# Domino_Single_Ethernet_No_Teardrop.net
KiCad netlist of a schematic drawn in EAGLE
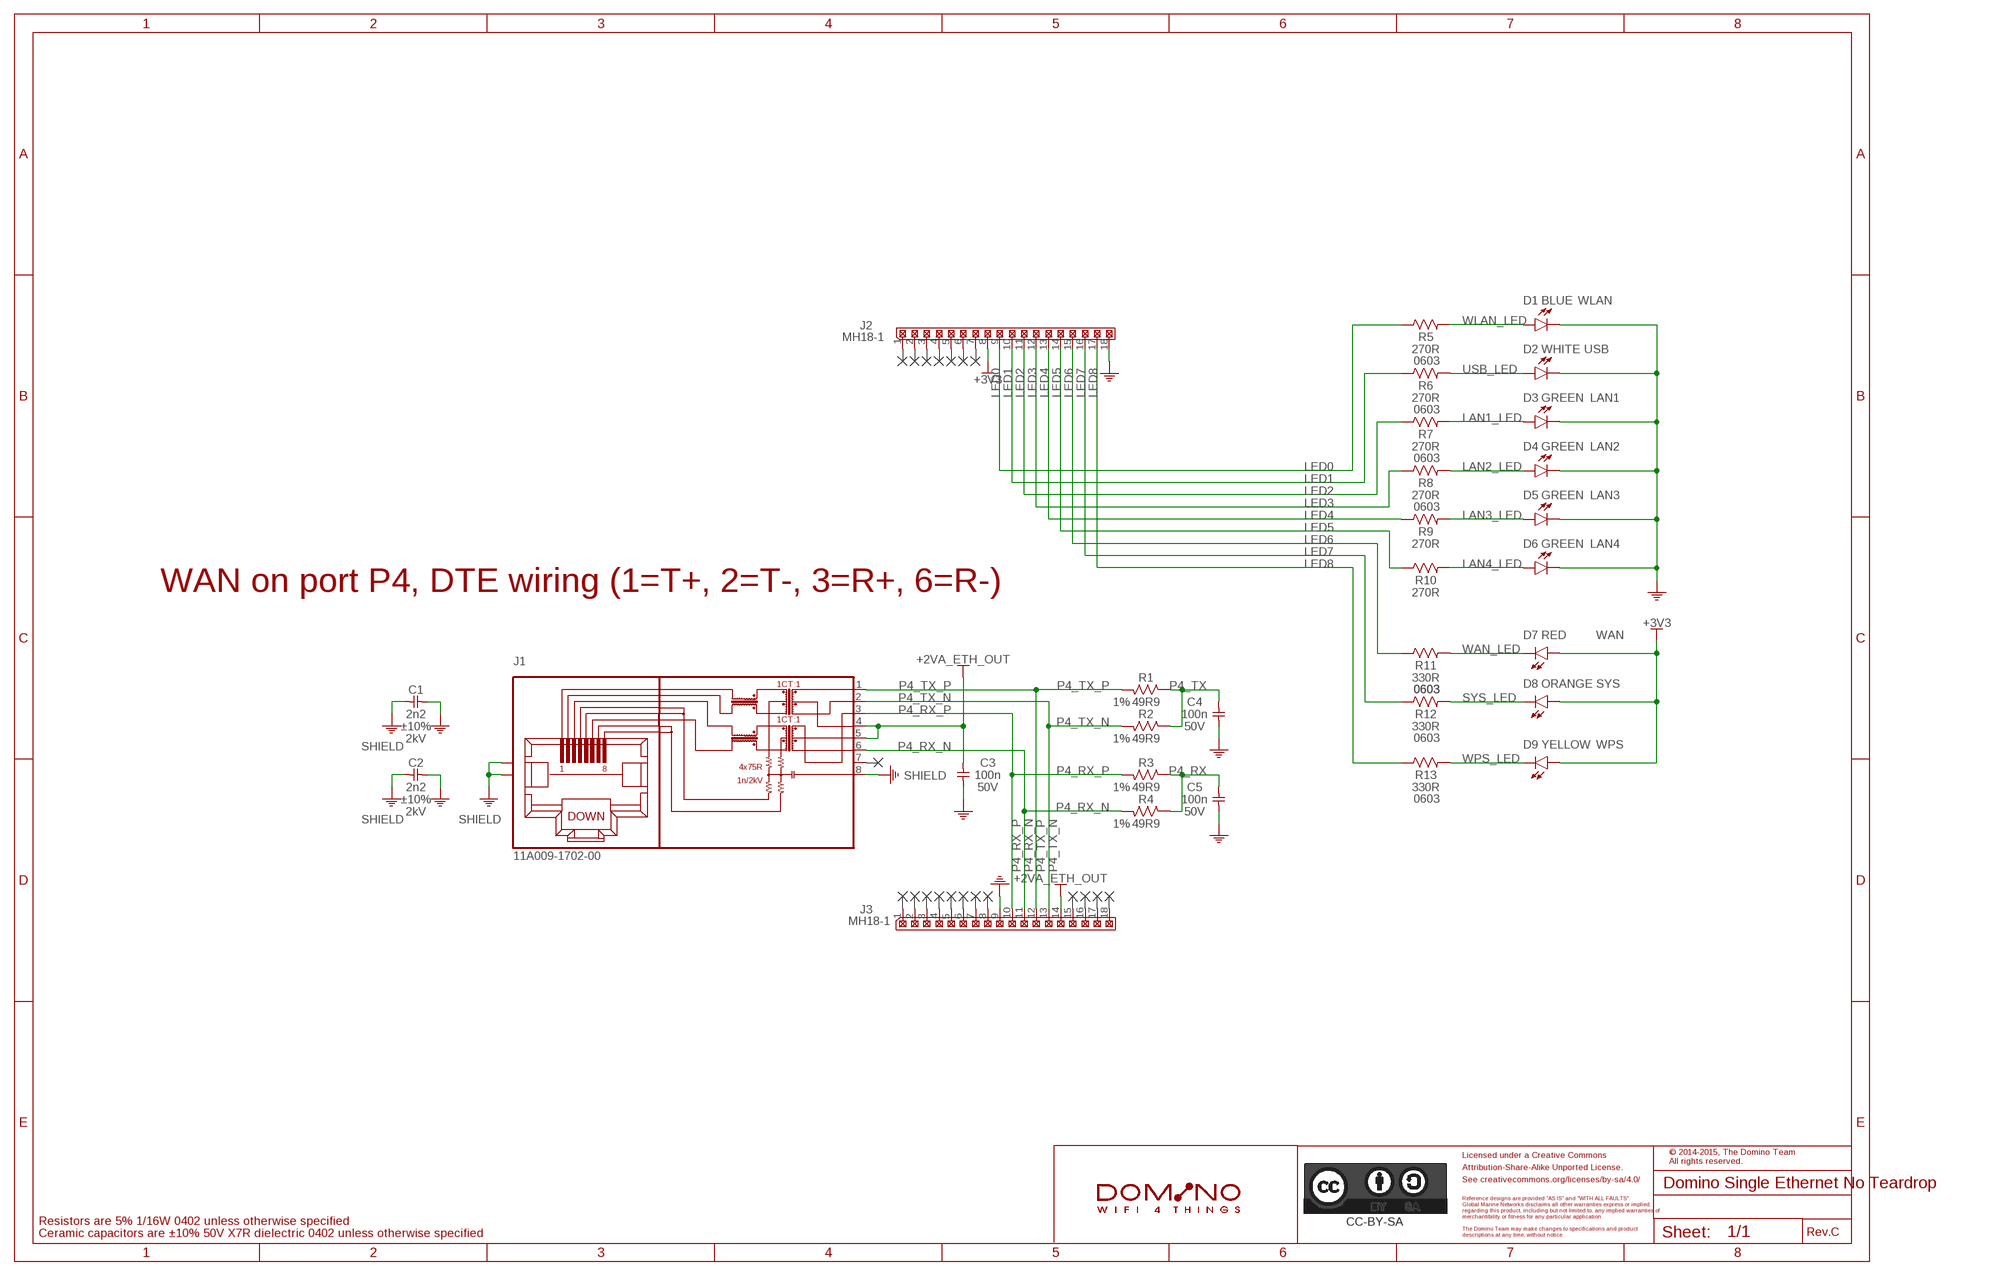
[diagram p0: schematic, sheet 1]

(export (version "E")
  (design (tool "Eeschema 10.0.6"))
  (components
    (comp (ref "C1")
      (value "2n2")
      (footprint "eagle-import:C1206")
      (fields
        (field (name "PARTNO") "C1210_2n2_X7R_10%_CER_2kV")
        (field (name "TOL") "±10%")
        (field (name "VOLT") "2kV")
      )
      (libsource (lib "eagle-import") (part "CAP_1206"))
    )
    (comp (ref "C2")
      (value "2n2")
      (footprint "eagle-import:C1206")
      (fields
        (field (name "PARTNO") "C1210_2n2_X7R_10%_CER_2kV")
        (field (name "TOL") "±10%")
        (field (name "VOLT") "2kV")
      )
      (libsource (lib "eagle-import") (part "CAP_1206"))
    )
    (comp (ref "C3")
      (value "100n")
      (footprint "eagle-import:C0402")
      (fields (field (name "PARTNO") "C0402_100n_X7R_10%_CER_50V") (field (name "VOLT") "50V"))
      (libsource (lib "eagle-import") (part "CAP_0402"))
    )
    (comp (ref "C4")
      (value "100n")
      (footprint "eagle-import:C0402")
      (fields (field (name "PARTNO") "C0402_100n_X7R_10%_CER_50V") (field (name "VOLT") "50V"))
      (libsource (lib "eagle-import") (part "CAP_0402"))
    )
    (comp (ref "C5")
      (value "100n")
      (footprint "eagle-import:C0402")
      (fields (field (name "PARTNO") "C0402_100n_X7R_10%_CER_50V") (field (name "VOLT") "50V"))
      (libsource (lib "eagle-import") (part "CAP_0402"))
    )
    (comp (ref "CC-BY-SA1")
      (value "CC-BY-SA_LOGO")
      (footprint "eagle-import:CC-BY-SA_LOGO")
      (libsource (lib "eagle-import") (part "CC-BY-SA_LOGO"))
    )
    (comp (ref "D1")
      (value "BLUE")
      (footprint "eagle-import:LED0603")
      (fields (field (name "PARTNO") "LED0603-BLUE"))
      (libsource (lib "eagle-import") (part "LED_0603"))
    )
    (comp (ref "D2")
      (value "WHITE")
      (footprint "eagle-import:LED0603")
      (fields (field (name "PARTNO") "LED0603-WHITE"))
      (libsource (lib "eagle-import") (part "LED_0603"))
    )
    (comp (ref "D3")
      (value "GREEN")
      (footprint "eagle-import:LED0603")
      (fields (field (name "PARTNO") "LED0603-GREEN"))
      (libsource (lib "eagle-import") (part "LED_0603"))
    )
    (comp (ref "D4")
      (value "GREEN")
      (footprint "eagle-import:LED0603")
      (fields (field (name "PARTNO") "LED0603-GREEN"))
      (libsource (lib "eagle-import") (part "LED_0603"))
    )
    (comp (ref "D5")
      (value "GREEN")
      (footprint "eagle-import:LED0603")
      (fields (field (name "PARTNO") "LED0603-GREEN"))
      (libsource (lib "eagle-import") (part "LED_0603"))
    )
    (comp (ref "D6")
      (value "GREEN")
      (footprint "eagle-import:LED0603")
      (fields (field (name "PARTNO") "LED0603-GREEN"))
      (libsource (lib "eagle-import") (part "LED_0603"))
    )
    (comp (ref "D7")
      (value "RED")
      (footprint "eagle-import:LED0603")
      (fields (field (name "PARTNO") "LED0603-ORANGE"))
      (libsource (lib "eagle-import") (part "LED_0603"))
    )
    (comp (ref "D8")
      (value "ORANGE")
      (footprint "eagle-import:LED0603")
      (fields (field (name "PARTNO") "LED0603-ORANGE"))
      (libsource (lib "eagle-import") (part "LED_0603"))
    )
    (comp (ref "D9")
      (value "YELLOW")
      (footprint "eagle-import:LED0603")
      (fields (field (name "PARTNO") "LED0603-YELLOW"))
      (libsource (lib "eagle-import") (part "LED_0603"))
    )
    (comp (ref "J1")
      (value "11A009-1702-00")
      (footprint "eagle-import:11A009-1702-00")
      (libsource (lib "eagle-import") (part "11A009-1702-00"))
    )
    (comp (ref "J2")
      (value "MH18-1")
      (footprint "eagle-import:MH18-1-0.1")
      (fields (field (name "PARTNO") "MH18-1-0.1"))
      (libsource (lib "eagle-import") (part "MH18-1"))
    )
    (comp (ref "J3")
      (value "MH18-1")
      (footprint "eagle-import:MH18-1-0.1")
      (fields (field (name "PARTNO") "MH18-1-0.1"))
      (libsource (lib "eagle-import") (part "MH18-1"))
    )
    (comp (ref "R1")
      (value "49R9")
      (footprint "eagle-import:R0402")
      (fields (field (name "PARTNO") "R0402_49R9_1%_62.5mW") (field (name "TOL") "1%"))
      (libsource (lib "eagle-import") (part "RES_0402"))
    )
    (comp (ref "R2")
      (value "49R9")
      (footprint "eagle-import:R0402")
      (fields (field (name "PARTNO") "R0402_49R9_1%_62.5mW") (field (name "TOL") "1%"))
      (libsource (lib "eagle-import") (part "RES_0402"))
    )
    (comp (ref "R3")
      (value "49R9")
      (footprint "eagle-import:R0402")
      (fields (field (name "PARTNO") "R0402_49R9_1%_62.5mW") (field (name "TOL") "1%"))
      (libsource (lib "eagle-import") (part "RES_0402"))
    )
    (comp (ref "R4")
      (value "49R9")
      (footprint "eagle-import:R0402")
      (fields (field (name "PARTNO") "R0402_49R9_1%_62.5mW") (field (name "TOL") "1%"))
      (libsource (lib "eagle-import") (part "RES_0402"))
    )
    (comp (ref "R5")
      (value "270R")
      (footprint "eagle-import:R0603")
      (fields (field (name "SIZE") "0603") (field (name "PARTNO") "R0603_270R_5%_125mW"))
      (libsource (lib "eagle-import") (part "RES_0603"))
    )
    (comp (ref "R6")
      (value "270R")
      (footprint "eagle-import:R0603")
      (fields (field (name "SIZE") "0603") (field (name "PARTNO") "R0603_270R_5%_125mW"))
      (libsource (lib "eagle-import") (part "RES_0603"))
    )
    (comp (ref "R7")
      (value "270R")
      (footprint "eagle-import:R0603")
      (fields (field (name "SIZE") "0603") (field (name "PARTNO") "R0603_270R_5%_125mW"))
      (libsource (lib "eagle-import") (part "RES_0603"))
    )
    (comp (ref "R8")
      (value "270R")
      (footprint "eagle-import:R0603")
      (fields (field (name "SIZE") "0603") (field (name "PARTNO") "R0603_270R_5%_125mW"))
      (libsource (lib "eagle-import") (part "RES_0603"))
    )
    (comp (ref "R9")
      (value "270R")
      (footprint "eagle-import:R0603")
      (fields (field (name "PARTNO") "R0603_270R_5%_125mW"))
      (libsource (lib "eagle-import") (part "RES_0603"))
    )
    (comp (ref "R10")
      (value "270R")
      (footprint "eagle-import:R0603")
      (fields (field (name "SIZE") "0603") (field (name "PARTNO") "R0603_270R_5%_125mW"))
      (libsource (lib "eagle-import") (part "RES_0603"))
    )
    (comp (ref "R11")
      (value "330R")
      (footprint "eagle-import:R0603")
      (fields (field (name "SIZE") "0603") (field (name "PARTNO") "R0603_330R_5%_125mW"))
      (libsource (lib "eagle-import") (part "RES_0603"))
    )
    (comp (ref "R12")
      (value "330R")
      (footprint "eagle-import:R0603")
      (fields (field (name "SIZE") "0603") (field (name "PARTNO") "R0603_330R_5%_125mW"))
      (libsource (lib "eagle-import") (part "RES_0603"))
    )
    (comp (ref "R13")
      (value "330R")
      (footprint "eagle-import:R0603")
      (fields (field (name "SIZE") "0603") (field (name "PARTNO") "R0603_330R_5%_125mW"))
      (libsource (lib "eagle-import") (part "RES_0603"))
    )
    (comp (ref "U$10")
      (value "DOMINO_LOGO")
      (footprint "eagle-import:DOMINO_LOGO")
      (libsource (lib "eagle-import") (part "DOMINO_LOGO"))
    )
  )
  (nets
    (net (code "1") (name "+2VA_ETH_OUT") (class "Default")
      (node (ref "C3") (pin "2") (pinfunction "2_2") (pintype "passive"))
      (node (ref "J1") (pin "4") (pinfunction "P4_4") (pintype "passive"))
      (node (ref "J1") (pin "5") (pinfunction "P5_5") (pintype "passive"))
      (node (ref "J3") (pin "14") (pinfunction "14_14") (pintype "passive"))
    )
    (net (code "2") (name "+3V3") (class "Default")
      (node (ref "D7") (pin "2") (pinfunction "A_2") (pintype "passive"))
      (node (ref "D8") (pin "2") (pinfunction "A_2") (pintype "passive"))
      (node (ref "D9") (pin "2") (pinfunction "A_2") (pintype "passive"))
      (node (ref "J2") (pin "8") (pinfunction "8_8") (pintype "passive"))
    )
    (net (code "3") (name "/LAN1_LED") (class "Default")
      (node (ref "D3") (pin "2") (pinfunction "A_2") (pintype "passive"))
      (node (ref "R7") (pin "2") (pinfunction "2_2") (pintype "passive"))
    )
    (net (code "4") (name "/LAN2_LED") (class "Default")
      (node (ref "D4") (pin "2") (pinfunction "A_2") (pintype "passive"))
      (node (ref "R8") (pin "2") (pinfunction "2_2") (pintype "passive"))
    )
    (net (code "5") (name "/LAN3_LED") (class "Default")
      (node (ref "D5") (pin "2") (pinfunction "A_2") (pintype "passive"))
      (node (ref "R9") (pin "2") (pinfunction "2_2") (pintype "passive"))
    )
    (net (code "6") (name "/LAN4_LED") (class "Default")
      (node (ref "D6") (pin "2") (pinfunction "A_2") (pintype "passive"))
      (node (ref "R10") (pin "2") (pinfunction "2_2") (pintype "passive"))
    )
    (net (code "7") (name "/LED0") (class "Default")
      (node (ref "J2") (pin "9") (pinfunction "9_9") (pintype "passive"))
      (node (ref "R5") (pin "1") (pinfunction "1_1") (pintype "passive"))
    )
    (net (code "8") (name "/LED1") (class "Default")
      (node (ref "J2") (pin "10") (pinfunction "10_10") (pintype "passive"))
      (node (ref "R6") (pin "1") (pinfunction "1_1") (pintype "passive"))
    )
    (net (code "9") (name "/LED2") (class "Default")
      (node (ref "J2") (pin "11") (pinfunction "11_11") (pintype "passive"))
      (node (ref "R7") (pin "1") (pinfunction "1_1") (pintype "passive"))
    )
    (net (code "10") (name "/LED3") (class "Default")
      (node (ref "J2") (pin "12") (pinfunction "12_12") (pintype "passive"))
      (node (ref "R8") (pin "1") (pinfunction "1_1") (pintype "passive"))
    )
    (net (code "11") (name "/LED4") (class "Default")
      (node (ref "J2") (pin "13") (pinfunction "13_13") (pintype "passive"))
      (node (ref "R9") (pin "1") (pinfunction "1_1") (pintype "passive"))
    )
    (net (code "12") (name "/LED5") (class "Default")
      (node (ref "J2") (pin "14") (pinfunction "14_14") (pintype "passive"))
      (node (ref "R10") (pin "1") (pinfunction "1_1") (pintype "passive"))
    )
    (net (code "13") (name "/LED6") (class "Default")
      (node (ref "J2") (pin "15") (pinfunction "15_15") (pintype "passive"))
      (node (ref "R11") (pin "1") (pinfunction "1_1") (pintype "passive"))
    )
    (net (code "14") (name "/LED7") (class "Default")
      (node (ref "J2") (pin "16") (pinfunction "16_16") (pintype "passive"))
      (node (ref "R12") (pin "1") (pinfunction "1_1") (pintype "passive"))
    )
    (net (code "15") (name "/LED8") (class "Default")
      (node (ref "J2") (pin "17") (pinfunction "17_17") (pintype "passive"))
      (node (ref "R13") (pin "1") (pinfunction "1_1") (pintype "passive"))
    )
    (net (code "16") (name "/P4_RX") (class "Default")
      (node (ref "C5") (pin "2") (pinfunction "2_2") (pintype "passive"))
      (node (ref "R3") (pin "1") (pinfunction "1_1") (pintype "passive"))
      (node (ref "R4") (pin "1") (pinfunction "1_1") (pintype "passive"))
    )
    (net (code "17") (name "/P4_RX_N") (class "Default")
      (node (ref "J1") (pin "6") (pinfunction "P6_6") (pintype "passive"))
      (node (ref "J3") (pin "11") (pinfunction "11_11") (pintype "passive"))
      (node (ref "R4") (pin "2") (pinfunction "2_2") (pintype "passive"))
    )
    (net (code "18") (name "/P4_RX_P") (class "Default")
      (node (ref "J1") (pin "3") (pinfunction "P3_3") (pintype "passive"))
      (node (ref "J3") (pin "10") (pinfunction "10_10") (pintype "passive"))
      (node (ref "R3") (pin "2") (pinfunction "2_2") (pintype "passive"))
    )
    (net (code "19") (name "/P4_TX") (class "Default")
      (node (ref "C4") (pin "2") (pinfunction "2_2") (pintype "passive"))
      (node (ref "R1") (pin "1") (pinfunction "1_1") (pintype "passive"))
      (node (ref "R2") (pin "1") (pinfunction "1_1") (pintype "passive"))
    )
    (net (code "20") (name "/P4_TX_N") (class "Default")
      (node (ref "J1") (pin "2") (pinfunction "P2_2") (pintype "passive"))
      (node (ref "J3") (pin "13") (pinfunction "13_13") (pintype "passive"))
      (node (ref "R2") (pin "2") (pinfunction "2_2") (pintype "passive"))
    )
    (net (code "21") (name "/P4_TX_P") (class "Default")
      (node (ref "J1") (pin "1") (pinfunction "P1_1") (pintype "passive"))
      (node (ref "J3") (pin "12") (pinfunction "12_12") (pintype "passive"))
      (node (ref "R1") (pin "2") (pinfunction "2_2") (pintype "passive"))
    )
    (net (code "22") (name "/SYS_LED") (class "Default")
      (node (ref "D8") (pin "1") (pinfunction "C_1") (pintype "passive"))
      (node (ref "R12") (pin "2") (pinfunction "2_2") (pintype "passive"))
    )
    (net (code "23") (name "/USB_LED") (class "Default")
      (node (ref "D2") (pin "2") (pinfunction "A_2") (pintype "passive"))
      (node (ref "R6") (pin "2") (pinfunction "2_2") (pintype "passive"))
    )
    (net (code "24") (name "/WAN_LED") (class "Default")
      (node (ref "D7") (pin "1") (pinfunction "C_1") (pintype "passive"))
      (node (ref "R11") (pin "2") (pinfunction "2_2") (pintype "passive"))
    )
    (net (code "25") (name "/WLAN_LED") (class "Default")
      (node (ref "D1") (pin "2") (pinfunction "A_2") (pintype "passive"))
      (node (ref "R5") (pin "2") (pinfunction "2_2") (pintype "passive"))
    )
    (net (code "26") (name "/WPS_LED") (class "Default")
      (node (ref "D9") (pin "1") (pinfunction "C_1") (pintype "passive"))
      (node (ref "R13") (pin "2") (pinfunction "2_2") (pintype "passive"))
    )
    (net (code "27") (name "GND") (class "Default")
      (node (ref "C1") (pin "1") (pinfunction "1_1") (pintype "passive"))
      (node (ref "C2") (pin "1") (pinfunction "1_1") (pintype "passive"))
      (node (ref "C3") (pin "1") (pinfunction "1_1") (pintype "passive"))
      (node (ref "C4") (pin "1") (pinfunction "1_1") (pintype "passive"))
      (node (ref "C5") (pin "1") (pinfunction "1_1") (pintype "passive"))
      (node (ref "D1") (pin "1") (pinfunction "C_1") (pintype "passive"))
      (node (ref "D2") (pin "1") (pinfunction "C_1") (pintype "passive"))
      (node (ref "D3") (pin "1") (pinfunction "C_1") (pintype "passive"))
      (node (ref "D4") (pin "1") (pinfunction "C_1") (pintype "passive"))
      (node (ref "D5") (pin "1") (pinfunction "C_1") (pintype "passive"))
      (node (ref "D6") (pin "1") (pinfunction "C_1") (pintype "passive"))
      (node (ref "J2") (pin "18") (pinfunction "18_18") (pintype "passive"))
      (node (ref "J3") (pin "9") (pinfunction "9_9") (pintype "passive"))
    )
    (net (code "28") (name "SHIELD") (class "Default")
      (node (ref "C1") (pin "2") (pinfunction "2_2") (pintype "passive"))
      (node (ref "C2") (pin "2") (pinfunction "2_2") (pintype "passive"))
      (node (ref "J1") (pin "8") (pinfunction "P8_8") (pintype "power_in"))
      (node (ref "J1") (pin "SH$1") (pinfunction "SHIELD_SH$1") (pintype "power_in"))
      (node (ref "J1") (pin "SH$2") (pinfunction "SHIELD_SH$2") (pintype "power_in"))
    )
    (net (code "29") (name "unconnected-(J1-P7-Pad7)") (class "Default")
      (node (ref "J1") (pin "7") (pinfunction "P7_7") (pintype "no_connect"))
    )
    (net (code "30") (name "unconnected-(J2-Pad1)") (class "Default")
      (node (ref "J2") (pin "1") (pinfunction "1_1") (pintype "passive"))
    )
    (net (code "31") (name "unconnected-(J2-Pad2)") (class "Default")
      (node (ref "J2") (pin "2") (pinfunction "2_2") (pintype "passive"))
    )
    (net (code "32") (name "unconnected-(J2-Pad3)") (class "Default")
      (node (ref "J2") (pin "3") (pinfunction "3_3") (pintype "passive"))
    )
    (net (code "33") (name "unconnected-(J2-Pad4)") (class "Default")
      (node (ref "J2") (pin "4") (pinfunction "4_4") (pintype "passive"))
    )
    (net (code "34") (name "unconnected-(J2-Pad5)") (class "Default")
      (node (ref "J2") (pin "5") (pinfunction "5_5") (pintype "passive"))
    )
    (net (code "35") (name "unconnected-(J2-Pad6)") (class "Default")
      (node (ref "J2") (pin "6") (pinfunction "6_6") (pintype "passive"))
    )
    (net (code "36") (name "unconnected-(J2-Pad7)") (class "Default")
      (node (ref "J2") (pin "7") (pinfunction "7_7") (pintype "passive"))
    )
    (net (code "37") (name "unconnected-(J3-Pad1)") (class "Default")
      (node (ref "J3") (pin "1") (pinfunction "1_1") (pintype "passive"))
    )
    (net (code "38") (name "unconnected-(J3-Pad2)") (class "Default")
      (node (ref "J3") (pin "2") (pinfunction "2_2") (pintype "passive"))
    )
    (net (code "39") (name "unconnected-(J3-Pad3)") (class "Default")
      (node (ref "J3") (pin "3") (pinfunction "3_3") (pintype "passive"))
    )
    (net (code "40") (name "unconnected-(J3-Pad4)") (class "Default")
      (node (ref "J3") (pin "4") (pinfunction "4_4") (pintype "passive"))
    )
    (net (code "41") (name "unconnected-(J3-Pad5)") (class "Default")
      (node (ref "J3") (pin "5") (pinfunction "5_5") (pintype "passive"))
    )
    (net (code "42") (name "unconnected-(J3-Pad6)") (class "Default")
      (node (ref "J3") (pin "6") (pinfunction "6_6") (pintype "passive"))
    )
    (net (code "43") (name "unconnected-(J3-Pad7)") (class "Default")
      (node (ref "J3") (pin "7") (pinfunction "7_7") (pintype "passive"))
    )
    (net (code "44") (name "unconnected-(J3-Pad8)") (class "Default")
      (node (ref "J3") (pin "8") (pinfunction "8_8") (pintype "passive"))
    )
    (net (code "45") (name "unconnected-(J3-Pad15)") (class "Default")
      (node (ref "J3") (pin "15") (pinfunction "15_15") (pintype "passive"))
    )
    (net (code "46") (name "unconnected-(J3-Pad16)") (class "Default")
      (node (ref "J3") (pin "16") (pinfunction "16_16") (pintype "passive"))
    )
    (net (code "47") (name "unconnected-(J3-Pad17)") (class "Default")
      (node (ref "J3") (pin "17") (pinfunction "17_17") (pintype "passive"))
    )
    (net (code "48") (name "unconnected-(J3-Pad18)") (class "Default")
      (node (ref "J3") (pin "18") (pinfunction "18_18") (pintype "passive"))
    )
  )
)
